# ButtonAndSwitches.net
KiCad netlist of a schematic drawn in Altium Designer
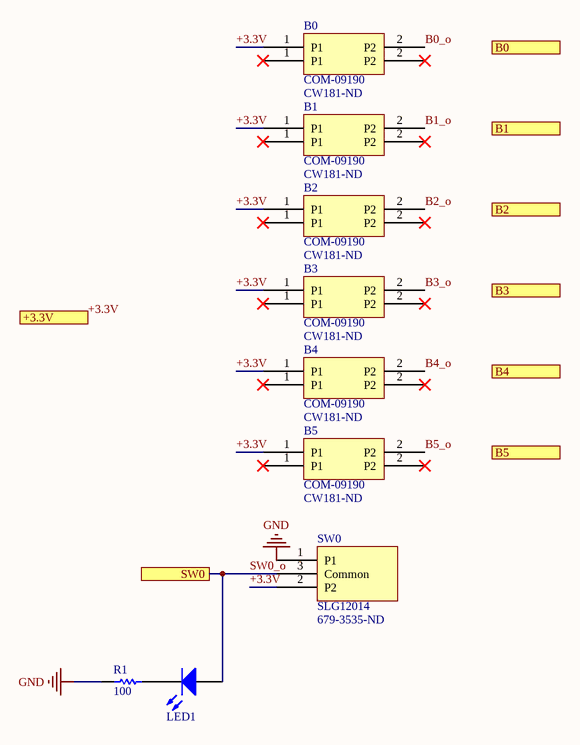
[diagram p0: ButtonAndSwitches.SchDoc]

(export (version "E")
  (design (tool "Eeschema 10.0.6"))
  (components
    (comp (ref "B0")
      (value "COM-09190")
      (footprint "COM-09190")
      (description "Momentary Pushbutton Switch - 12mm Square")
      (fields (field (name "SUPPLIER PART NUMBER 1") "CW181-ND"))
      (libsource (lib "ServoInterface") (part "Push Button_Tactile"))
    )
    (comp (ref "B1")
      (value "COM-09190")
      (footprint "COM-09190")
      (description "Momentary Pushbutton Switch - 12mm Square")
      (fields (field (name "SUPPLIER PART NUMBER 1") "CW181-ND"))
      (libsource (lib "ServoInterface") (part "Push Button_Tactile"))
    )
    (comp (ref "B2")
      (value "COM-09190")
      (footprint "COM-09190")
      (description "Momentary Pushbutton Switch - 12mm Square")
      (fields (field (name "SUPPLIER PART NUMBER 1") "CW181-ND"))
      (libsource (lib "ServoInterface") (part "Push Button_Tactile"))
    )
    (comp (ref "B3")
      (value "COM-09190")
      (footprint "COM-09190")
      (description "Momentary Pushbutton Switch - 12mm Square")
      (fields (field (name "SUPPLIER PART NUMBER 1") "CW181-ND"))
      (libsource (lib "ServoInterface") (part "Push Button_Tactile"))
    )
    (comp (ref "B4")
      (value "COM-09190")
      (footprint "COM-09190")
      (description "Momentary Pushbutton Switch - 12mm Square")
      (fields (field (name "SUPPLIER PART NUMBER 1") "CW181-ND"))
      (libsource (lib "ServoInterface") (part "Push Button_Tactile"))
    )
    (comp (ref "B5")
      (value "COM-09190")
      (footprint "COM-09190")
      (description "Momentary Pushbutton Switch - 12mm Square")
      (fields (field (name "SUPPLIER PART NUMBER 1") "CW181-ND"))
      (libsource (lib "ServoInterface") (part "Push Button_Tactile"))
    )
    (comp (ref "LED1")
      (value "LTL-4223")
      (footprint "LED Through")
      (description "2 V drop 10 mA Red")
      (libsource (lib "ServoInterface") (part "LED_RED"))
    )
    (comp (ref "R1")
      (value "100")
      (footprint "Resistor Through Hole")
      (description "CF14JT100R")
      (libsource (lib "ServoInterface") (part "Resistor_100"))
    )
    (comp (ref "SW0")
      (value "SLG12014")
      (footprint "SLG12014")
      (description "SWITCH SLIDE SPDT 300MA 125V")
      (fields (field (name "SUPPLIER PART NUMBER 1") "679-3535-ND"))
      (libsource (lib "ServoInterface") (part "SlideSwitch"))
    )
  )
  (nets
    (net (code "1") (name "/+3.3V") (class "Default")
      (node (ref "B0") (pin "1") (pinfunction "P1_1") (pintype "passive"))
      (node (ref "B1") (pin "1") (pinfunction "P1_1") (pintype "passive"))
      (node (ref "B2") (pin "1") (pinfunction "P1_1") (pintype "passive"))
      (node (ref "B3") (pin "1") (pinfunction "P1_1") (pintype "passive"))
      (node (ref "B4") (pin "1") (pinfunction "P1_1") (pintype "passive"))
      (node (ref "B5") (pin "1") (pinfunction "P1_1") (pintype "passive"))
      (node (ref "SW0") (pin "2") (pinfunction "P2_2") (pintype "passive"))
    )
    (net (code "3") (name "/B0_o") (class "Default")
      (node (ref "B0") (pin "2") (pinfunction "P2_2") (pintype "passive"))
    )
    (net (code "5") (name "/B1_o") (class "Default")
      (node (ref "B1") (pin "2") (pinfunction "P2_2") (pintype "passive"))
    )
    (net (code "7") (name "/B2_o") (class "Default")
      (node (ref "B2") (pin "2") (pinfunction "P2_2") (pintype "passive"))
    )
    (net (code "9") (name "/B3_o") (class "Default")
      (node (ref "B3") (pin "2") (pinfunction "P2_2") (pintype "passive"))
    )
    (net (code "11") (name "/B4_o") (class "Default")
      (node (ref "B4") (pin "2") (pinfunction "P2_2") (pintype "passive"))
    )
    (net (code "13") (name "/B5_o") (class "Default")
      (node (ref "B5") (pin "2") (pinfunction "P2_2") (pintype "passive"))
    )
    (net (code "14") (name "/SW0_o") (class "Default")
      (node (ref "LED1") (pin "1") (pinfunction "A_1") (pintype "passive"))
      (node (ref "SW0") (pin "3") (pinfunction "Common_3") (pintype "passive"))
    )
    (net (code "15") (name "GND") (class "Default")
      (node (ref "R1") (pin "2") (pinfunction "2_2") (pintype "passive"))
      (node (ref "SW0") (pin "1") (pinfunction "P1_1") (pintype "passive"))
    )
    (net (code "16") (name "Net-(LED1-K)") (class "Default")
      (node (ref "LED1") (pin "2") (pinfunction "K_2") (pintype "passive"))
      (node (ref "R1") (pin "1") (pinfunction "1_1") (pintype "passive"))
    )
    (net (code "17") (name "unconnected-(B0-P1-Pad1)") (class "Default")
      (node (ref "B0") (pin "1") (pinfunction "P1_1") (pintype "passive+no_connect"))
    )
    (net (code "18") (name "unconnected-(B0-P2-Pad2)") (class "Default")
      (node (ref "B0") (pin "2") (pinfunction "P2_2") (pintype "passive+no_connect"))
    )
    (net (code "19") (name "unconnected-(B1-P1-Pad1)") (class "Default")
      (node (ref "B1") (pin "1") (pinfunction "P1_1") (pintype "passive+no_connect"))
    )
    (net (code "20") (name "unconnected-(B1-P2-Pad2)") (class "Default")
      (node (ref "B1") (pin "2") (pinfunction "P2_2") (pintype "passive+no_connect"))
    )
    (net (code "21") (name "unconnected-(B2-P1-Pad1)") (class "Default")
      (node (ref "B2") (pin "1") (pinfunction "P1_1") (pintype "passive+no_connect"))
    )
    (net (code "22") (name "unconnected-(B2-P2-Pad2)") (class "Default")
      (node (ref "B2") (pin "2") (pinfunction "P2_2") (pintype "passive+no_connect"))
    )
    (net (code "23") (name "unconnected-(B3-P1-Pad1)") (class "Default")
      (node (ref "B3") (pin "1") (pinfunction "P1_1") (pintype "passive+no_connect"))
    )
    (net (code "24") (name "unconnected-(B3-P2-Pad2)") (class "Default")
      (node (ref "B3") (pin "2") (pinfunction "P2_2") (pintype "passive+no_connect"))
    )
    (net (code "25") (name "unconnected-(B4-P1-Pad1)") (class "Default")
      (node (ref "B4") (pin "1") (pinfunction "P1_1") (pintype "passive+no_connect"))
    )
    (net (code "26") (name "unconnected-(B4-P2-Pad2)") (class "Default")
      (node (ref "B4") (pin "2") (pinfunction "P2_2") (pintype "passive+no_connect"))
    )
    (net (code "27") (name "unconnected-(B5-P1-Pad1)") (class "Default")
      (node (ref "B5") (pin "1") (pinfunction "P1_1") (pintype "passive+no_connect"))
    )
    (net (code "28") (name "unconnected-(B5-P2-Pad2)") (class "Default")
      (node (ref "B5") (pin "2") (pinfunction "P2_2") (pintype "passive+no_connect"))
    )
  )
)
